# WideRangeVoltmeter.net
KiCad netlist of a schematic drawn in Altium Designer
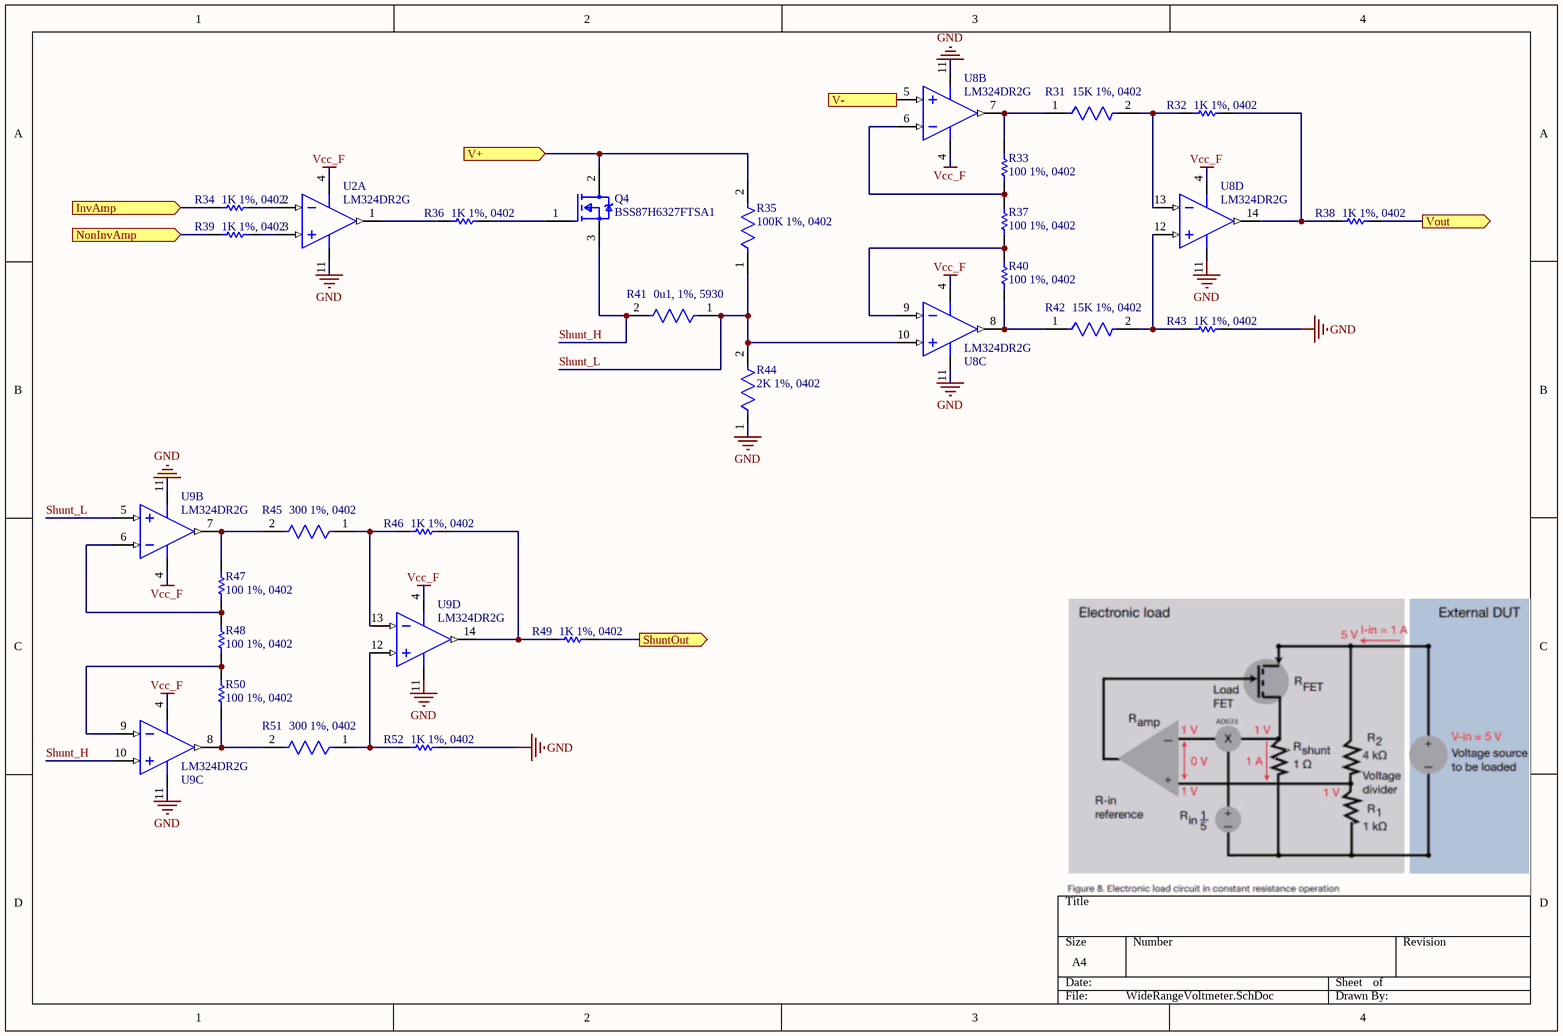
[diagram p0: WideRangeVoltmeter.SchDoc]

(export (version "E")
  (design (tool "Eeschema 10.0.6"))
  (components
    (comp (ref "Q4")
      (value "BSS87H6327FTSA1")
      (footprint "FP-PG-SOT89-4-MFG")
      (description "MOSFET N-CH 240V 260MA SOT89-4")
      (libsource (lib "Altium Content Vault") (part "0f782e8fd7e4ef74ecff6fccd0a82c3"))
    )
    (comp (ref "R31")
      (value "15K 1%, 0402")
      (footprint "FP-ERJ2R-MFG")
      (description "RES SMD 15K OHM 1% 1/10W 0402")
      (fields (field (name "TOLERANCE") "1%") (field (name "MANUFACTURER PART NUMBER") "ERJ-2RKF1502X"))
      (libsource (lib "Altium Content Vault") (part "1029c3af85768c4190bb7ad29bc67b5"))
    )
    (comp (ref "R32")
      (value "1K 1%, 0402")
      (footprint "RESC1005X40X25NL05T05")
      (description "Chip Resistor, 1 KOhm, +/- 1%, 100 mW, -55 to 155 degC, 0402 (1005 Metric), RoHS, Tape and Reel")
      (fields (field (name "PARTNUMBER") "ERJ-2RKF1001X") (field (name "MANUFACTURER") "Basic Passives"))
      (libsource (lib "Altium Content Vault") (part "RES-2"))
    )
    (comp (ref "R33")
      (value "100 1%, 0402")
      (footprint "RESC1005X40X25LL05T05")
      (description "Chip Resistor, 100 Ohm, +/- 1%, 100 mW, -55 to 155 degC, 0402 (1005 Metric), RoHS, Tape and Reel")
      (fields (field (name "MANUFACTURER") "Basic Passives") (field (name "TOLERANCE") "1%"))
      (libsource (lib "Altium Content Vault") (part "RES-2"))
    )
    (comp (ref "R34")
      (value "1K 1%, 0402")
      (footprint "RESC1005X40X25NL05T05")
      (description "Chip Resistor, 1 KOhm, +/- 1%, 100 mW, -55 to 155 degC, 0402 (1005 Metric), RoHS, Tape and Reel")
      (fields (field (name "PARTNUMBER") "ERJ-2RKF1001X") (field (name "MANUFACTURER") "Basic Passives"))
      (libsource (lib "Altium Content Vault") (part "RES-2"))
    )
    (comp (ref "R35")
      (value "100K 1%, 0402")
      (footprint "FP-ERJ2RK-IPC_C")
      (description "RES SMD 100K OHM 1% 1/10W 0402")
      (fields (field (name "TOLERANCE") "1%"))
      (libsource (lib "Altium Content Vault") (part "1029c3af85768c4190bb7ad29bc67b5"))
    )
    (comp (ref "R36")
      (value "1K 1%, 0402")
      (footprint "RESC1005X40X25NL05T05")
      (description "Chip Resistor, 1 KOhm, +/- 1%, 100 mW, -55 to 155 degC, 0402 (1005 Metric), RoHS, Tape and Reel")
      (fields (field (name "PARTNUMBER") "ERJ-2RKF1001X") (field (name "MANUFACTURER") "Basic Passives"))
      (libsource (lib "Altium Content Vault") (part "RES-2"))
    )
    (comp (ref "R37")
      (value "100 1%, 0402")
      (footprint "RESC1005X40X25LL05T05")
      (description "Chip Resistor, 100 Ohm, +/- 1%, 100 mW, -55 to 155 degC, 0402 (1005 Metric), RoHS, Tape and Reel")
      (fields (field (name "MANUFACTURER") "Basic Passives") (field (name "TOLERANCE") "1%"))
      (libsource (lib "Altium Content Vault") (part "RES-2"))
    )
    (comp (ref "R38")
      (value "1K 1%, 0402")
      (footprint "RESC1005X40X25NL05T05")
      (description "Chip Resistor, 1 KOhm, +/- 1%, 100 mW, -55 to 155 degC, 0402 (1005 Metric), RoHS, Tape and Reel")
      (fields (field (name "PARTNUMBER") "ERJ-2RKF1001X") (field (name "MANUFACTURER") "Basic Passives"))
      (libsource (lib "Altium Content Vault") (part "RES-2"))
    )
    (comp (ref "R39")
      (value "1K 1%, 0402")
      (footprint "RESC1005X40X25NL05T05")
      (description "Chip Resistor, 1 KOhm, +/- 1%, 100 mW, -55 to 155 degC, 0402 (1005 Metric), RoHS, Tape and Reel")
      (fields (field (name "PARTNUMBER") "ERJ-2RKF1001X") (field (name "MANUFACTURER") "Basic Passives"))
      (libsource (lib "Altium Content Vault") (part "RES-2"))
    )
    (comp (ref "R40")
      (value "100 1%, 0402")
      (footprint "RESC1005X40X25LL05T05")
      (description "Chip Resistor, 100 Ohm, +/- 1%, 100 mW, -55 to 155 degC, 0402 (1005 Metric), RoHS, Tape and Reel")
      (fields (field (name "MANUFACTURER") "Basic Passives") (field (name "TOLERANCE") "1%"))
      (libsource (lib "Altium Content Vault") (part "RES-2"))
    )
    (comp (ref "R41")
      (value "0u1, 1%, 5930")
      (footprint "FP-CSS2H-5930K-1L00F-MFG")
      (description "CSS2H-5930K-1L00F Res Metal Strip 5930 0.001 Ohm 1% 9W ±50ppm/C Pad SMD Automotive T/R")
      (fields (field (name "TOLERANCE") "1%"))
      (libsource (lib "Altium Content Vault") (part "1029c3af85768c4190bb7ad29bc67b5"))
    )
    (comp (ref "R42")
      (value "15K 1%, 0402")
      (footprint "FP-ERJ2R-MFG")
      (description "RES SMD 15K OHM 1% 1/10W 0402")
      (fields (field (name "TOLERANCE") "1%") (field (name "MANUFACTURER PART NUMBER") "ERJ-2RKF1502X"))
      (libsource (lib "Altium Content Vault") (part "1029c3af85768c4190bb7ad29bc67b5"))
    )
    (comp (ref "R43")
      (value "1K 1%, 0402")
      (footprint "RESC1005X40X25NL05T05")
      (description "Chip Resistor, 1 KOhm, +/- 1%, 100 mW, -55 to 155 degC, 0402 (1005 Metric), RoHS, Tape and Reel")
      (fields (field (name "PARTNUMBER") "ERJ-2RKF1001X") (field (name "MANUFACTURER") "Basic Passives"))
      (libsource (lib "Altium Content Vault") (part "RES-2"))
    )
    (comp (ref "R44")
      (value "2K 1%, 0402")
      (footprint "FP-ERJ2RK-MFG")
      (description "RES SMD 2K OHM 1% 1/10W 0402")
      (fields (field (name "TOLERANCE") "1%"))
      (libsource (lib "Altium Content Vault") (part "1029c3af85768c4190bb7ad29bc67b5"))
    )
    (comp (ref "R45")
      (value "300 1%, 0402")
      (footprint "FP-ERJ2RK-IPC_A")
      (description "RES SMD 300 OHM 1% 1/10W 0402")
      (fields (field (name "TOLERANCE") "1%"))
      (libsource (lib "Altium Content Vault") (part "1029c3af85768c4190bb7ad29bc67b5"))
    )
    (comp (ref "R46")
      (value "1K 1%, 0402")
      (footprint "RESC1005X40X25NL05T05")
      (description "Chip Resistor, 1 KOhm, +/- 1%, 100 mW, -55 to 155 degC, 0402 (1005 Metric), RoHS, Tape and Reel")
      (fields (field (name "PARTNUMBER") "ERJ-2RKF1001X") (field (name "MANUFACTURER") "Basic Passives"))
      (libsource (lib "Altium Content Vault") (part "RES-2"))
    )
    (comp (ref "R47")
      (value "100 1%, 0402")
      (footprint "RESC1005X40X25LL05T05")
      (description "Chip Resistor, 100 Ohm, +/- 1%, 100 mW, -55 to 155 degC, 0402 (1005 Metric), RoHS, Tape and Reel")
      (fields (field (name "MANUFACTURER") "Basic Passives") (field (name "TOLERANCE") "1%"))
      (libsource (lib "Altium Content Vault") (part "RES-2"))
    )
    (comp (ref "R48")
      (value "100 1%, 0402")
      (footprint "RESC1005X40X25LL05T05")
      (description "Chip Resistor, 100 Ohm, +/- 1%, 100 mW, -55 to 155 degC, 0402 (1005 Metric), RoHS, Tape and Reel")
      (fields (field (name "MANUFACTURER") "Basic Passives") (field (name "TOLERANCE") "1%"))
      (libsource (lib "Altium Content Vault") (part "RES-2"))
    )
    (comp (ref "R49")
      (value "1K 1%, 0402")
      (footprint "RESC1005X40X25NL05T05")
      (description "Chip Resistor, 1 KOhm, +/- 1%, 100 mW, -55 to 155 degC, 0402 (1005 Metric), RoHS, Tape and Reel")
      (fields (field (name "PARTNUMBER") "ERJ-2RKF1001X") (field (name "MANUFACTURER") "Basic Passives"))
      (libsource (lib "Altium Content Vault") (part "RES-2"))
    )
    (comp (ref "R50")
      (value "100 1%, 0402")
      (footprint "RESC1005X40X25LL05T05")
      (description "Chip Resistor, 100 Ohm, +/- 1%, 100 mW, -55 to 155 degC, 0402 (1005 Metric), RoHS, Tape and Reel")
      (fields (field (name "MANUFACTURER") "Basic Passives") (field (name "TOLERANCE") "1%"))
      (libsource (lib "Altium Content Vault") (part "RES-2"))
    )
    (comp (ref "R51")
      (value "300 1%, 0402")
      (footprint "FP-ERJ2RK-IPC_A")
      (description "RES SMD 300 OHM 1% 1/10W 0402")
      (fields (field (name "TOLERANCE") "1%"))
      (libsource (lib "Altium Content Vault") (part "1029c3af85768c4190bb7ad29bc67b5"))
    )
    (comp (ref "R52")
      (value "1K 1%, 0402")
      (footprint "RESC1005X40X25NL05T05")
      (description "Chip Resistor, 1 KOhm, +/- 1%, 100 mW, -55 to 155 degC, 0402 (1005 Metric), RoHS, Tape and Reel")
      (fields (field (name "PARTNUMBER") "ERJ-2RKF1001X") (field (name "MANUFACTURER") "Basic Passives"))
      (libsource (lib "Altium Content Vault") (part "RES-2"))
    )
    (comp (ref "U2")
      (value "LM324DR2G")
      (footprint "ONSC-SOIC-14-751A-03_V")
      (fields (field (name "MANUFACTURER") "On Semiconductor"))
      (libsource (lib "Altium Content Vault") (part "ONSC-LM224_324_2902_NCV2902-14"))
    )
    (comp (ref "U8")
      (value "LM324DR2G")
      (footprint "ONSC-SOIC-14-751A-03_V")
      (fields (field (name "MANUFACTURER") "On Semiconductor"))
      (libsource (lib "Altium Content Vault") (part "ONSC-LM224_324_2902_NCV2902-14"))
    )
    (comp (ref "U9")
      (value "LM324DR2G")
      (footprint "ONSC-SOIC-14-751A-03_V")
      (fields (field (name "MANUFACTURER") "On Semiconductor"))
      (libsource (lib "Altium Content Vault") (part "ONSC-LM224_324_2902_NCV2902-14"))
    )
  )
  (nets
    (net (code "1") (name "/InvAmp") (class "Default")
      (node (ref "R34") (pin "1") (pinfunction "1_1") (pintype "passive"))
    )
    (net (code "2") (name "/NonInvAmp") (class "Default")
      (node (ref "R39") (pin "1") (pinfunction "1_1") (pintype "passive"))
    )
    (net (code "3") (name "/ShuntOut") (class "Default")
      (node (ref "R49") (pin "2") (pinfunction "2_2") (pintype "passive"))
    )
    (net (code "4") (name "/Shunt_H") (class "Default")
      (node (ref "Q4") (pin "3") (pinfunction "Source_3") (pintype "passive"))
      (node (ref "R41") (pin "2") (pinfunction "2_2") (pintype "passive"))
      (node (ref "U9") (pin "10") (pinfunction "IN3+_10") (pintype "input"))
    )
    (net (code "5") (name "/Shunt_L") (class "Default")
      (node (ref "R35") (pin "1") (pinfunction "1_1") (pintype "passive"))
      (node (ref "R41") (pin "1") (pinfunction "1_1") (pintype "passive"))
      (node (ref "R44") (pin "2") (pinfunction "2_2") (pintype "passive"))
      (node (ref "U8") (pin "10") (pinfunction "IN3+_10") (pintype "input"))
      (node (ref "U9") (pin "5") (pinfunction "IN2+_5") (pintype "input"))
    )
    (net (code "6") (name "/V+") (class "Default")
      (node (ref "Q4") (pin "2") (pinfunction "Drain_2") (pintype "passive"))
      (node (ref "R35") (pin "2") (pinfunction "2_2") (pintype "passive"))
    )
    (net (code "7") (name "/V-") (class "Default")
      (node (ref "U8") (pin "5") (pinfunction "IN2+_5") (pintype "input"))
    )
    (net (code "8") (name "/Vout") (class "Default")
      (node (ref "R38") (pin "2") (pinfunction "2_2") (pintype "passive"))
    )
    (net (code "9") (name "GND") (class "Default")
      (node (ref "R43") (pin "2") (pinfunction "2_2") (pintype "passive"))
      (node (ref "R44") (pin "1") (pinfunction "1_1") (pintype "passive"))
      (node (ref "R52") (pin "2") (pinfunction "2_2") (pintype "passive"))
      (node (ref "U2") (pin "11") (pinfunction "VEE/GND_11") (pintype "power_in"))
      (node (ref "U8") (pin "11") (pinfunction "VEE/GND_11") (pintype "power_in"))
      (node (ref "U9") (pin "11") (pinfunction "VEE/GND_11") (pintype "power_in"))
    )
    (net (code "10") (name "Net-(Q4-Gate)") (class "Default")
      (node (ref "Q4") (pin "1") (pinfunction "Gate_1") (pintype "passive"))
      (node (ref "R36") (pin "2") (pinfunction "2_2") (pintype "passive"))
    )
    (net (code "11") (name "Net-(U2A-IN1+)") (class "Default")
      (node (ref "R39") (pin "2") (pinfunction "2_2") (pintype "passive"))
      (node (ref "U2") (pin "3") (pinfunction "IN1+_3") (pintype "input"))
    )
    (net (code "12") (name "Net-(U2A-IN1-)") (class "Default")
      (node (ref "R34") (pin "2") (pinfunction "2_2") (pintype "passive"))
      (node (ref "U2") (pin "2") (pinfunction "IN1-_2") (pintype "input"))
    )
    (net (code "13") (name "Net-(U2A-OUT1)") (class "Default")
      (node (ref "R36") (pin "1") (pinfunction "1_1") (pintype "passive"))
      (node (ref "U2") (pin "1") (pinfunction "OUT1_1") (pintype "output"))
    )
    (net (code "14") (name "Net-(U8B-IN2-)") (class "Default")
      (node (ref "R33") (pin "1") (pinfunction "1_1") (pintype "passive"))
      (node (ref "R37") (pin "2") (pinfunction "2_2") (pintype "passive"))
      (node (ref "U8") (pin "6") (pinfunction "IN2-_6") (pintype "input"))
    )
    (net (code "15") (name "Net-(U8B-OUT2)") (class "Default")
      (node (ref "R31") (pin "1") (pinfunction "1_1") (pintype "passive"))
      (node (ref "R33") (pin "2") (pinfunction "2_2") (pintype "passive"))
      (node (ref "U8") (pin "7") (pinfunction "OUT2_7") (pintype "output"))
    )
    (net (code "16") (name "Net-(U8C-IN3-)") (class "Default")
      (node (ref "R37") (pin "1") (pinfunction "1_1") (pintype "passive"))
      (node (ref "R40") (pin "2") (pinfunction "2_2") (pintype "passive"))
      (node (ref "U8") (pin "9") (pinfunction "IN3-_9") (pintype "input"))
    )
    (net (code "17") (name "Net-(U8C-OUT3)") (class "Default")
      (node (ref "R40") (pin "1") (pinfunction "1_1") (pintype "passive"))
      (node (ref "R42") (pin "1") (pinfunction "1_1") (pintype "passive"))
      (node (ref "U8") (pin "8") (pinfunction "OUT3_8") (pintype "output"))
    )
    (net (code "18") (name "Net-(U8D-IN4+)") (class "Default")
      (node (ref "R42") (pin "2") (pinfunction "2_2") (pintype "passive"))
      (node (ref "R43") (pin "1") (pinfunction "1_1") (pintype "passive"))
      (node (ref "U8") (pin "12") (pinfunction "IN4+_12") (pintype "input"))
    )
    (net (code "19") (name "Net-(U8D-IN4-)") (class "Default")
      (node (ref "R31") (pin "2") (pinfunction "2_2") (pintype "passive"))
      (node (ref "R32") (pin "1") (pinfunction "1_1") (pintype "passive"))
      (node (ref "U8") (pin "13") (pinfunction "IN4-_13") (pintype "input"))
    )
    (net (code "20") (name "Net-(U8D-OUT4)") (class "Default")
      (node (ref "R32") (pin "2") (pinfunction "2_2") (pintype "passive"))
      (node (ref "R38") (pin "1") (pinfunction "1_1") (pintype "passive"))
      (node (ref "U8") (pin "14") (pinfunction "OUT4_14") (pintype "output"))
    )
    (net (code "21") (name "Net-(U9B-IN2-)") (class "Default")
      (node (ref "R47") (pin "1") (pinfunction "1_1") (pintype "passive"))
      (node (ref "R48") (pin "2") (pinfunction "2_2") (pintype "passive"))
      (node (ref "U9") (pin "6") (pinfunction "IN2-_6") (pintype "input"))
    )
    (net (code "22") (name "Net-(U9B-OUT2)") (class "Default")
      (node (ref "R45") (pin "2") (pinfunction "2_2") (pintype "passive"))
      (node (ref "R47") (pin "2") (pinfunction "2_2") (pintype "passive"))
      (node (ref "U9") (pin "7") (pinfunction "OUT2_7") (pintype "output"))
    )
    (net (code "23") (name "Net-(U9C-IN3-)") (class "Default")
      (node (ref "R48") (pin "1") (pinfunction "1_1") (pintype "passive"))
      (node (ref "R50") (pin "2") (pinfunction "2_2") (pintype "passive"))
      (node (ref "U9") (pin "9") (pinfunction "IN3-_9") (pintype "input"))
    )
    (net (code "24") (name "Net-(U9C-OUT3)") (class "Default")
      (node (ref "R50") (pin "1") (pinfunction "1_1") (pintype "passive"))
      (node (ref "R51") (pin "2") (pinfunction "2_2") (pintype "passive"))
      (node (ref "U9") (pin "8") (pinfunction "OUT3_8") (pintype "output"))
    )
    (net (code "25") (name "Net-(U9D-IN4+)") (class "Default")
      (node (ref "R51") (pin "1") (pinfunction "1_1") (pintype "passive"))
      (node (ref "R52") (pin "1") (pinfunction "1_1") (pintype "passive"))
      (node (ref "U9") (pin "12") (pinfunction "IN4+_12") (pintype "input"))
    )
    (net (code "26") (name "Net-(U9D-IN4-)") (class "Default")
      (node (ref "R45") (pin "1") (pinfunction "1_1") (pintype "passive"))
      (node (ref "R46") (pin "1") (pinfunction "1_1") (pintype "passive"))
      (node (ref "U9") (pin "13") (pinfunction "IN4-_13") (pintype "input"))
    )
    (net (code "27") (name "Net-(U9D-OUT4)") (class "Default")
      (node (ref "R46") (pin "2") (pinfunction "2_2") (pintype "passive"))
      (node (ref "R49") (pin "1") (pinfunction "1_1") (pintype "passive"))
      (node (ref "U9") (pin "14") (pinfunction "OUT4_14") (pintype "output"))
    )
    (net (code "28") (name "Vcc_F") (class "Default")
      (node (ref "U2") (pin "4") (pinfunction "VCC_4") (pintype "power_in"))
      (node (ref "U8") (pin "4") (pinfunction "VCC_4") (pintype "power_in"))
      (node (ref "U9") (pin "4") (pinfunction "VCC_4") (pintype "power_in"))
    )
    (net (code "29") (name "unconnected-(U8D-VEE{slash}GND-Pad11)") (class "Default")
      (node (ref "U8") (pin "11") (pinfunction "VEE/GND_11") (pintype "power_in"))
    )
    (net (code "30") (name "unconnected-(U9D-VEE{slash}GND-Pad11)") (class "Default")
      (node (ref "U9") (pin "11") (pinfunction "VEE/GND_11") (pintype "power_in"))
    )
  )
)
